# MazeSolverPCB.net
KiCad netlist of a schematic drawn in EAGLE
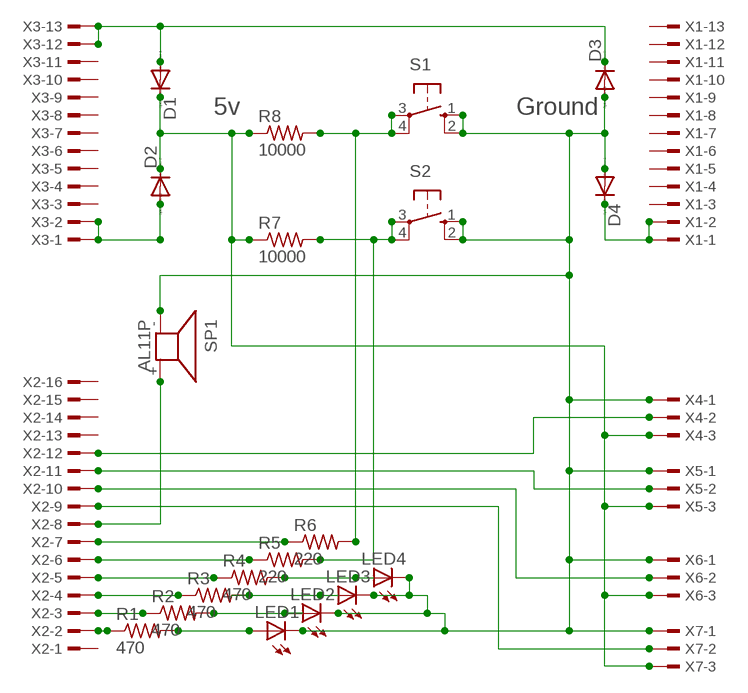
[diagram p0: schematic, sheet 1]

(export (version "E")
  (design (tool "Eeschema 10.0.6"))
  (components
    (comp (ref "D1")
      (value "1N4004")
      (footprint "eagle-import:DO41-10")
      (libsource (lib "eagle-import") (part "1N4004"))
    )
    (comp (ref "D2")
      (value "1N4004")
      (footprint "eagle-import:DO41-10")
      (libsource (lib "eagle-import") (part "1N4004"))
    )
    (comp (ref "D3")
      (value "1N4004")
      (footprint "eagle-import:DO41-10")
      (libsource (lib "eagle-import") (part "1N4004"))
    )
    (comp (ref "D4")
      (value "1N4004")
      (footprint "eagle-import:DO41-10")
      (libsource (lib "eagle-import") (part "1N4004"))
    )
    (comp (ref "LED1")
      (value "TLLG4400")
      (footprint "eagle-import:LED3MM")
      (fields (field (name "MF") "VISHAY SEMICONDUCTOR"))
      (libsource (lib "eagle-import") (part "TLLG4400"))
    )
    (comp (ref "LED2")
      (value "TLLG4400")
      (footprint "eagle-import:LED3MM")
      (fields (field (name "MF") "VISHAY SEMICONDUCTOR"))
      (libsource (lib "eagle-import") (part "TLLG4400"))
    )
    (comp (ref "LED3")
      (value "TLLG4400")
      (footprint "eagle-import:LED3MM")
      (fields (field (name "MF") "VISHAY SEMICONDUCTOR"))
      (libsource (lib "eagle-import") (part "TLLG4400"))
    )
    (comp (ref "LED4")
      (value "TLLG4400")
      (footprint "eagle-import:LED3MM")
      (fields (field (name "MF") "VISHAY SEMICONDUCTOR"))
      (libsource (lib "eagle-import") (part "TLLG4400"))
    )
    (comp (ref "R1")
      (value "470")
      (footprint "eagle-import:0207_7")
      (libsource (lib "eagle-import") (part "R-US_0207/7"))
    )
    (comp (ref "R2")
      (value "470")
      (footprint "eagle-import:0207_7")
      (libsource (lib "eagle-import") (part "R-US_0207/7"))
    )
    (comp (ref "R3")
      (value "470")
      (footprint "eagle-import:0207_7")
      (libsource (lib "eagle-import") (part "R-US_0207/7"))
    )
    (comp (ref "R4")
      (value "470")
      (footprint "eagle-import:0207_7")
      (libsource (lib "eagle-import") (part "R-US_0207/7"))
    )
    (comp (ref "R5")
      (value "220")
      (footprint "eagle-import:0207_7")
      (libsource (lib "eagle-import") (part "R-US_0207/7"))
    )
    (comp (ref "R6")
      (value "220")
      (footprint "eagle-import:0207_7")
      (libsource (lib "eagle-import") (part "R-US_0207/7"))
    )
    (comp (ref "R7")
      (value "10000")
      (footprint "eagle-import:0207_7")
      (libsource (lib "eagle-import") (part "R-US_0207/7"))
    )
    (comp (ref "R8")
      (value "10000")
      (footprint "eagle-import:0207_7")
      (libsource (lib "eagle-import") (part "R-US_0207/7"))
    )
    (comp (ref "S1")
      (value "10-XX")
      (footprint "eagle-import:B3F-10XX")
      (fields (field (name "MPN") "B3F-1000"))
      (libsource (lib "eagle-import") (part "10-XX"))
    )
    (comp (ref "S2")
      (value "10-XX")
      (footprint "eagle-import:B3F-10XX")
      (fields (field (name "MPN") "B3F-1000"))
      (libsource (lib "eagle-import") (part "10-XX"))
    )
    (comp (ref "SP1")
      (value "AL11P")
      (footprint "eagle-import:AL11P")
      (libsource (lib "eagle-import") (part "AL11P"))
    )
    (comp (ref "X1")
      (value "TSW-113-02-S-S")
      (footprint "eagle-import:TSW-113-02-S-S")
      (libsource (lib "eagle-import") (part "TSW-113-02-S-S"))
    )
    (comp (ref "X2")
      (value "TSW-116-02-S-S")
      (footprint "eagle-import:TSW-116-02-S-S")
      (libsource (lib "eagle-import") (part "TSW-116-02-S-S"))
    )
    (comp (ref "X3")
      (value "TSW-113-02-S-S")
      (footprint "eagle-import:TSW-113-02-S-S")
      (libsource (lib "eagle-import") (part "TSW-113-02-S-S"))
    )
    (comp (ref "X4")
      (value "TSW-103-02-S-S")
      (footprint "eagle-import:TSW-103-02-S-S")
      (libsource (lib "eagle-import") (part "TSW-103-02-S-S"))
    )
    (comp (ref "X5")
      (value "TSW-103-02-S-S")
      (footprint "eagle-import:TSW-103-02-S-S")
      (libsource (lib "eagle-import") (part "TSW-103-02-S-S"))
    )
    (comp (ref "X6")
      (value "TSW-103-02-S-S")
      (footprint "eagle-import:TSW-103-02-S-S")
      (libsource (lib "eagle-import") (part "TSW-103-02-S-S"))
    )
    (comp (ref "X7")
      (value "TSW-103-02-S-S")
      (footprint "eagle-import:TSW-103-02-S-S")
      (libsource (lib "eagle-import") (part "TSW-103-02-S-S"))
    )
  )
  (nets
    (net (code "1") (name "Net-(LED1-C)") (class "Default")
      (node (ref "D3") (pin "A") (pinfunction "A_A") (pintype "passive"))
      (node (ref "D4") (pin "A") (pinfunction "A_A") (pintype "passive"))
      (node (ref "LED1") (pin "K") (pinfunction "C_K") (pintype "passive"))
      (node (ref "LED2") (pin "K") (pinfunction "C_K") (pintype "passive"))
      (node (ref "LED3") (pin "K") (pinfunction "C_K") (pintype "passive"))
      (node (ref "LED4") (pin "K") (pinfunction "C_K") (pintype "passive"))
      (node (ref "S1") (pin "1") (pinfunction "S_1") (pintype "passive"))
      (node (ref "S1") (pin "2") (pinfunction "S1_2") (pintype "passive"))
      (node (ref "S2") (pin "1") (pinfunction "S_1") (pintype "passive"))
      (node (ref "S2") (pin "2") (pinfunction "S1_2") (pintype "passive"))
      (node (ref "SP1") (pin "-") (pinfunction "1_-") (pintype "passive"))
      (node (ref "X4") (pin "1") (pinfunction "1_1") (pintype "passive"))
      (node (ref "X5") (pin "1") (pinfunction "1_1") (pintype "passive"))
      (node (ref "X6") (pin "1") (pinfunction "1_1") (pintype "passive"))
      (node (ref "X7") (pin "1") (pinfunction "1_1") (pintype "passive"))
    )
    (net (code "2") (name "Net-(LED1-PadA)") (class "Default")
      (node (ref "LED1") (pin "A") (pinfunction "A_A") (pintype "passive"))
      (node (ref "R1") (pin "2") (pinfunction "2_2") (pintype "passive"))
    )
    (net (code "3") (name "Net-(LED2-PadA)") (class "Default")
      (node (ref "LED2") (pin "A") (pinfunction "A_A") (pintype "passive"))
      (node (ref "R2") (pin "2") (pinfunction "2_2") (pintype "passive"))
    )
    (net (code "4") (name "Net-(LED3-PadA)") (class "Default")
      (node (ref "LED3") (pin "A") (pinfunction "A_A") (pintype "passive"))
      (node (ref "R3") (pin "2") (pinfunction "2_2") (pintype "passive"))
    )
    (net (code "5") (name "Net-(LED4-PadA)") (class "Default")
      (node (ref "LED4") (pin "A") (pinfunction "A_A") (pintype "passive"))
      (node (ref "R4") (pin "2") (pinfunction "2_2") (pintype "passive"))
    )
    (net (code "6") (name "Net-(S1-P)") (class "Default")
      (node (ref "R6") (pin "2") (pinfunction "2_2") (pintype "passive"))
      (node (ref "R8") (pin "2") (pinfunction "2_2") (pintype "passive"))
      (node (ref "S1") (pin "3") (pinfunction "P_3") (pintype "passive"))
      (node (ref "S1") (pin "4") (pinfunction "P1_4") (pintype "passive"))
    )
    (net (code "7") (name "Net-(S2-P)") (class "Default")
      (node (ref "R5") (pin "2") (pinfunction "2_2") (pintype "passive"))
      (node (ref "R7") (pin "2") (pinfunction "2_2") (pintype "passive"))
      (node (ref "S2") (pin "3") (pinfunction "P_3") (pintype "passive"))
      (node (ref "S2") (pin "4") (pinfunction "P1_4") (pintype "passive"))
    )
    (net (code "8") (name "Net-(SP1-2)") (class "Default")
      (node (ref "SP1") (pin "+") (pinfunction "2_+") (pintype "passive"))
      (node (ref "X2") (pin "8") (pinfunction "1_8") (pintype "passive"))
    )
    (net (code "9") (name "Net-(X1F-1)") (class "Default")
      (node (ref "D4") (pin "C") (pinfunction "C_C") (pintype "passive"))
      (node (ref "X1") (pin "1") (pinfunction "1_1") (pintype "passive"))
      (node (ref "X1") (pin "2") (pinfunction "1_2") (pintype "passive"))
    )
    (net (code "10") (name "Net-(X2B-1)") (class "Default")
      (node (ref "X2") (pin "10") (pinfunction "1_10") (pintype "passive"))
      (node (ref "X6") (pin "2") (pinfunction "1_2") (pintype "passive"))
    )
    (net (code "11") (name "Net-(X2C-1)") (class "Default")
      (node (ref "X2") (pin "11") (pinfunction "1_11") (pintype "passive"))
      (node (ref "X5") (pin "2") (pinfunction "1_2") (pintype "passive"))
    )
    (net (code "12") (name "Net-(X2D-1)") (class "Default")
      (node (ref "X2") (pin "12") (pinfunction "1_12") (pintype "passive"))
      (node (ref "X4") (pin "2") (pinfunction "1_2") (pintype "passive"))
    )
    (net (code "13") (name "Net-(X2I-1)") (class "Default")
      (node (ref "R1") (pin "1") (pinfunction "1_1") (pintype "passive"))
      (node (ref "X2") (pin "2") (pinfunction "1_2") (pintype "passive"))
    )
    (net (code "14") (name "Net-(X2J-1)") (class "Default")
      (node (ref "R2") (pin "1") (pinfunction "1_1") (pintype "passive"))
      (node (ref "X2") (pin "3") (pinfunction "1_3") (pintype "passive"))
    )
    (net (code "15") (name "Net-(X2K-1)") (class "Default")
      (node (ref "R3") (pin "1") (pinfunction "1_1") (pintype "passive"))
      (node (ref "X2") (pin "4") (pinfunction "1_4") (pintype "passive"))
    )
    (net (code "16") (name "Net-(X2L-1)") (class "Default")
      (node (ref "R4") (pin "1") (pinfunction "1_1") (pintype "passive"))
      (node (ref "X2") (pin "5") (pinfunction "1_5") (pintype "passive"))
    )
    (net (code "17") (name "Net-(X2M-1)") (class "Default")
      (node (ref "R5") (pin "1") (pinfunction "1_1") (pintype "passive"))
      (node (ref "X2") (pin "6") (pinfunction "1_6") (pintype "passive"))
    )
    (net (code "18") (name "Net-(X2N-1)") (class "Default")
      (node (ref "R6") (pin "1") (pinfunction "1_1") (pintype "passive"))
      (node (ref "X2") (pin "7") (pinfunction "1_7") (pintype "passive"))
    )
    (net (code "19") (name "Net-(X2P-1)") (class "Default")
      (node (ref "X2") (pin "9") (pinfunction "1_9") (pintype "passive"))
      (node (ref "X7") (pin "2") (pinfunction "1_2") (pintype "passive"))
    )
    (net (code "20") (name "Net-(X3D-1)") (class "Default")
      (node (ref "D1") (pin "A") (pinfunction "A_A") (pintype "passive"))
      (node (ref "D3") (pin "C") (pinfunction "C_C") (pintype "passive"))
      (node (ref "X3") (pin "12") (pinfunction "1_12") (pintype "passive"))
      (node (ref "X3") (pin "13") (pinfunction "1_13") (pintype "passive"))
    )
    (net (code "21") (name "Net-(X3F-1)") (class "Default")
      (node (ref "D2") (pin "A") (pinfunction "A_A") (pintype "passive"))
      (node (ref "X3") (pin "1") (pinfunction "1_1") (pintype "passive"))
      (node (ref "X3") (pin "2") (pinfunction "1_2") (pintype "passive"))
    )
    (net (code "22") (name "Net-(X4C-1)") (class "Default")
      (node (ref "D1") (pin "C") (pinfunction "C_C") (pintype "passive"))
      (node (ref "D2") (pin "C") (pinfunction "C_C") (pintype "passive"))
      (node (ref "R7") (pin "1") (pinfunction "1_1") (pintype "passive"))
      (node (ref "R8") (pin "1") (pinfunction "1_1") (pintype "passive"))
      (node (ref "X4") (pin "3") (pinfunction "1_3") (pintype "passive"))
      (node (ref "X5") (pin "3") (pinfunction "1_3") (pintype "passive"))
      (node (ref "X6") (pin "3") (pinfunction "1_3") (pintype "passive"))
      (node (ref "X7") (pin "3") (pinfunction "1_3") (pintype "passive"))
    )
    (net (code "23") (name "unconnected-(X1B-1-Pad10)") (class "Default")
      (node (ref "X1") (pin "10") (pinfunction "1_10") (pintype "passive"))
    )
    (net (code "24") (name "unconnected-(X1C-1-Pad11)") (class "Default")
      (node (ref "X1") (pin "11") (pinfunction "1_11") (pintype "passive"))
    )
    (net (code "25") (name "unconnected-(X1D-1-Pad12)") (class "Default")
      (node (ref "X1") (pin "12") (pinfunction "1_12") (pintype "passive"))
    )
    (net (code "26") (name "unconnected-(X1E-1-Pad13)") (class "Default")
      (node (ref "X1") (pin "13") (pinfunction "1_13") (pintype "passive"))
    )
    (net (code "27") (name "unconnected-(X1G-1-Pad3)") (class "Default")
      (node (ref "X1") (pin "3") (pinfunction "1_3") (pintype "passive"))
    )
    (net (code "28") (name "unconnected-(X1H-1-Pad4)") (class "Default")
      (node (ref "X1") (pin "4") (pinfunction "1_4") (pintype "passive"))
    )
    (net (code "29") (name "unconnected-(X1I-1-Pad5)") (class "Default")
      (node (ref "X1") (pin "5") (pinfunction "1_5") (pintype "passive"))
    )
    (net (code "30") (name "unconnected-(X1J-1-Pad6)") (class "Default")
      (node (ref "X1") (pin "6") (pinfunction "1_6") (pintype "passive"))
    )
    (net (code "31") (name "unconnected-(X1K-1-Pad7)") (class "Default")
      (node (ref "X1") (pin "7") (pinfunction "1_7") (pintype "passive"))
    )
    (net (code "32") (name "unconnected-(X1L-1-Pad8)") (class "Default")
      (node (ref "X1") (pin "8") (pinfunction "1_8") (pintype "passive"))
    )
    (net (code "33") (name "unconnected-(X1M-1-Pad9)") (class "Default")
      (node (ref "X1") (pin "9") (pinfunction "1_9") (pintype "passive"))
    )
    (net (code "34") (name "unconnected-(X2-Pad1)") (class "Default")
      (node (ref "X2") (pin "1") (pinfunction "1_1") (pintype "passive"))
    )
    (net (code "35") (name "unconnected-(X2E-1-Pad13)") (class "Default")
      (node (ref "X2") (pin "13") (pinfunction "1_13") (pintype "passive"))
    )
    (net (code "36") (name "unconnected-(X2F-1-Pad14)") (class "Default")
      (node (ref "X2") (pin "14") (pinfunction "1_14") (pintype "passive"))
    )
    (net (code "37") (name "unconnected-(X2G-1-Pad15)") (class "Default")
      (node (ref "X2") (pin "15") (pinfunction "1_15") (pintype "passive"))
    )
    (net (code "38") (name "unconnected-(X2H-1-Pad16)") (class "Default")
      (node (ref "X2") (pin "16") (pinfunction "1_16") (pintype "passive"))
    )
    (net (code "39") (name "unconnected-(X3B-1-Pad10)") (class "Default")
      (node (ref "X3") (pin "10") (pinfunction "1_10") (pintype "passive"))
    )
    (net (code "40") (name "unconnected-(X3C-1-Pad11)") (class "Default")
      (node (ref "X3") (pin "11") (pinfunction "1_11") (pintype "passive"))
    )
    (net (code "41") (name "unconnected-(X3G-1-Pad3)") (class "Default")
      (node (ref "X3") (pin "3") (pinfunction "1_3") (pintype "passive"))
    )
    (net (code "42") (name "unconnected-(X3H-1-Pad4)") (class "Default")
      (node (ref "X3") (pin "4") (pinfunction "1_4") (pintype "passive"))
    )
    (net (code "43") (name "unconnected-(X3I-1-Pad5)") (class "Default")
      (node (ref "X3") (pin "5") (pinfunction "1_5") (pintype "passive"))
    )
    (net (code "44") (name "unconnected-(X3J-1-Pad6)") (class "Default")
      (node (ref "X3") (pin "6") (pinfunction "1_6") (pintype "passive"))
    )
    (net (code "45") (name "unconnected-(X3K-1-Pad7)") (class "Default")
      (node (ref "X3") (pin "7") (pinfunction "1_7") (pintype "passive"))
    )
    (net (code "46") (name "unconnected-(X3L-1-Pad8)") (class "Default")
      (node (ref "X3") (pin "8") (pinfunction "1_8") (pintype "passive"))
    )
    (net (code "47") (name "unconnected-(X3M-1-Pad9)") (class "Default")
      (node (ref "X3") (pin "9") (pinfunction "1_9") (pintype "passive"))
    )
  )
)
